# sch.net
KiCad netlist of a schematic drawn in Altium Designer
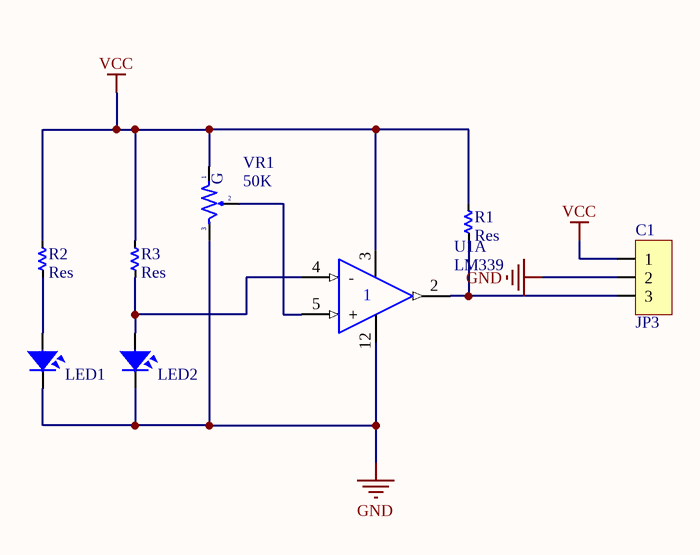
[diagram p0: sch.SchDoc]

(export (version "E")
  (design (tool "Eeschema 10.0.6"))
  (components
    (comp (ref "C1")
      (value "JP3")
      (footprint "JP3-C1T")
      (description "WR-PHD 2.54 mm Angled Socket Header")
      (fields
        (field (name "MANUFACTURER") "Würth Elektronik eiSos GmbH")
        (field (name "PARTNO") "613003143121")
        (field (name "CREATED BY") "Karrer Zheng")
      )
      (libsource (lib "Thư Viện Altium FULL HD") (part "JP3"))
    )
    (comp (ref "LED1")
      (value "LED")
      (footprint "LED-5-WHITE")
      (description "LED Single colour Green and Red")
      (libsource (lib "Thư Viện Altium FULL HD") (part "LED"))
    )
    (comp (ref "LED2")
      (value "LED")
      (footprint "LED-5-WHITE")
      (description "LED Single colour Green and Red")
      (libsource (lib "Thư Viện Altium FULL HD") (part "LED"))
    )
    (comp (ref "R1")
      (value "Res")
      (footprint "RES-1/4W-SMALL")
      (fields
        (field (name "MANUFACTURER") "Generic Components")
        (field (name "PUBLISHER") "Altium Hobart Technology Centre")
      )
      (libsource (lib "Thư Viện Altium FULL HD") (part "Res"))
    )
    (comp (ref "R2")
      (value "Res")
      (footprint "RES-1/4W-SMALL")
      (fields
        (field (name "MANUFACTURER") "Generic Components")
        (field (name "PUBLISHER") "Altium Hobart Technology Centre")
      )
      (libsource (lib "Thư Viện Altium FULL HD") (part "Res"))
    )
    (comp (ref "R3")
      (value "Res")
      (footprint "RES-1/4W-SMALL")
      (fields
        (field (name "MANUFACTURER") "Generic Components")
        (field (name "PUBLISHER") "Altium Hobart Technology Centre")
      )
      (libsource (lib "Thư Viện Altium FULL HD") (part "Res"))
    )
    (comp (ref "U1")
      (value "LM339")
      (footprint "DIP14")
      (description "Low Power Low Offset Voltage Quad Comparators")
      (libsource (lib "Thư Viện Altium FULL HD") (part "LM339"))
    )
    (comp (ref "VR1")
      (value "50K")
      (footprint "VR-S1")
      (description "Var Resistor")
      (libsource (lib "Thư Viện Altium FULL HD") (part "VR-S"))
    )
  )
  (nets
    (net (code "1") (name "GND") (class "Default")
      (node (ref "C1") (pin "2") (pinfunction "2_2") (pintype "passive"))
      (node (ref "LED1") (pin "2") (pinfunction "2_2") (pintype "passive"))
      (node (ref "LED2") (pin "2") (pinfunction "2_2") (pintype "passive"))
      (node (ref "U1") (pin "12") (pinfunction "GND_12") (pintype "power_in"))
      (node (ref "VR1") (pin "3") (pinfunction "3_3") (pintype "passive"))
    )
    (net (code "2") (name "Net-(LED1-Pad1)") (class "Default")
      (node (ref "LED1") (pin "1") (pinfunction "1_1") (pintype "passive"))
      (node (ref "R2") (pin "2") (pinfunction "2_2") (pintype "passive"))
    )
    (net (code "3") (name "Net-(U1A-+)") (class "Default")
      (node (ref "U1") (pin "5") (pinfunction "+_5") (pintype "input"))
      (node (ref "VR1") (pin "2") (pinfunction "2_2") (pintype "passive"))
    )
    (net (code "4") (name "Net-(U1A--)") (class "Default")
      (node (ref "LED2") (pin "1") (pinfunction "1_1") (pintype "passive"))
      (node (ref "R3") (pin "2") (pinfunction "2_2") (pintype "passive"))
      (node (ref "U1") (pin "4") (pinfunction "-_4") (pintype "input"))
    )
    (net (code "5") (name "Net-(U1A-OUT)") (class "Default")
      (node (ref "C1") (pin "3") (pinfunction "3_3") (pintype "passive"))
      (node (ref "R1") (pin "2") (pinfunction "2_2") (pintype "passive"))
      (node (ref "U1") (pin "2") (pinfunction "OUT_2") (pintype "output"))
    )
    (net (code "6") (name "VCC") (class "Default")
      (node (ref "C1") (pin "1") (pinfunction "1_1") (pintype "passive"))
      (node (ref "R1") (pin "1") (pinfunction "1_1") (pintype "passive"))
      (node (ref "R2") (pin "1") (pinfunction "1_1") (pintype "passive"))
      (node (ref "R3") (pin "1") (pinfunction "1_1") (pintype "passive"))
      (node (ref "U1") (pin "3") (pinfunction "VCC_3") (pintype "power_in"))
      (node (ref "VR1") (pin "1") (pinfunction "1_1") (pintype "passive"))
    )
  )
)
